# CANduino.net
KiCad netlist of a schematic drawn in Altium Designer
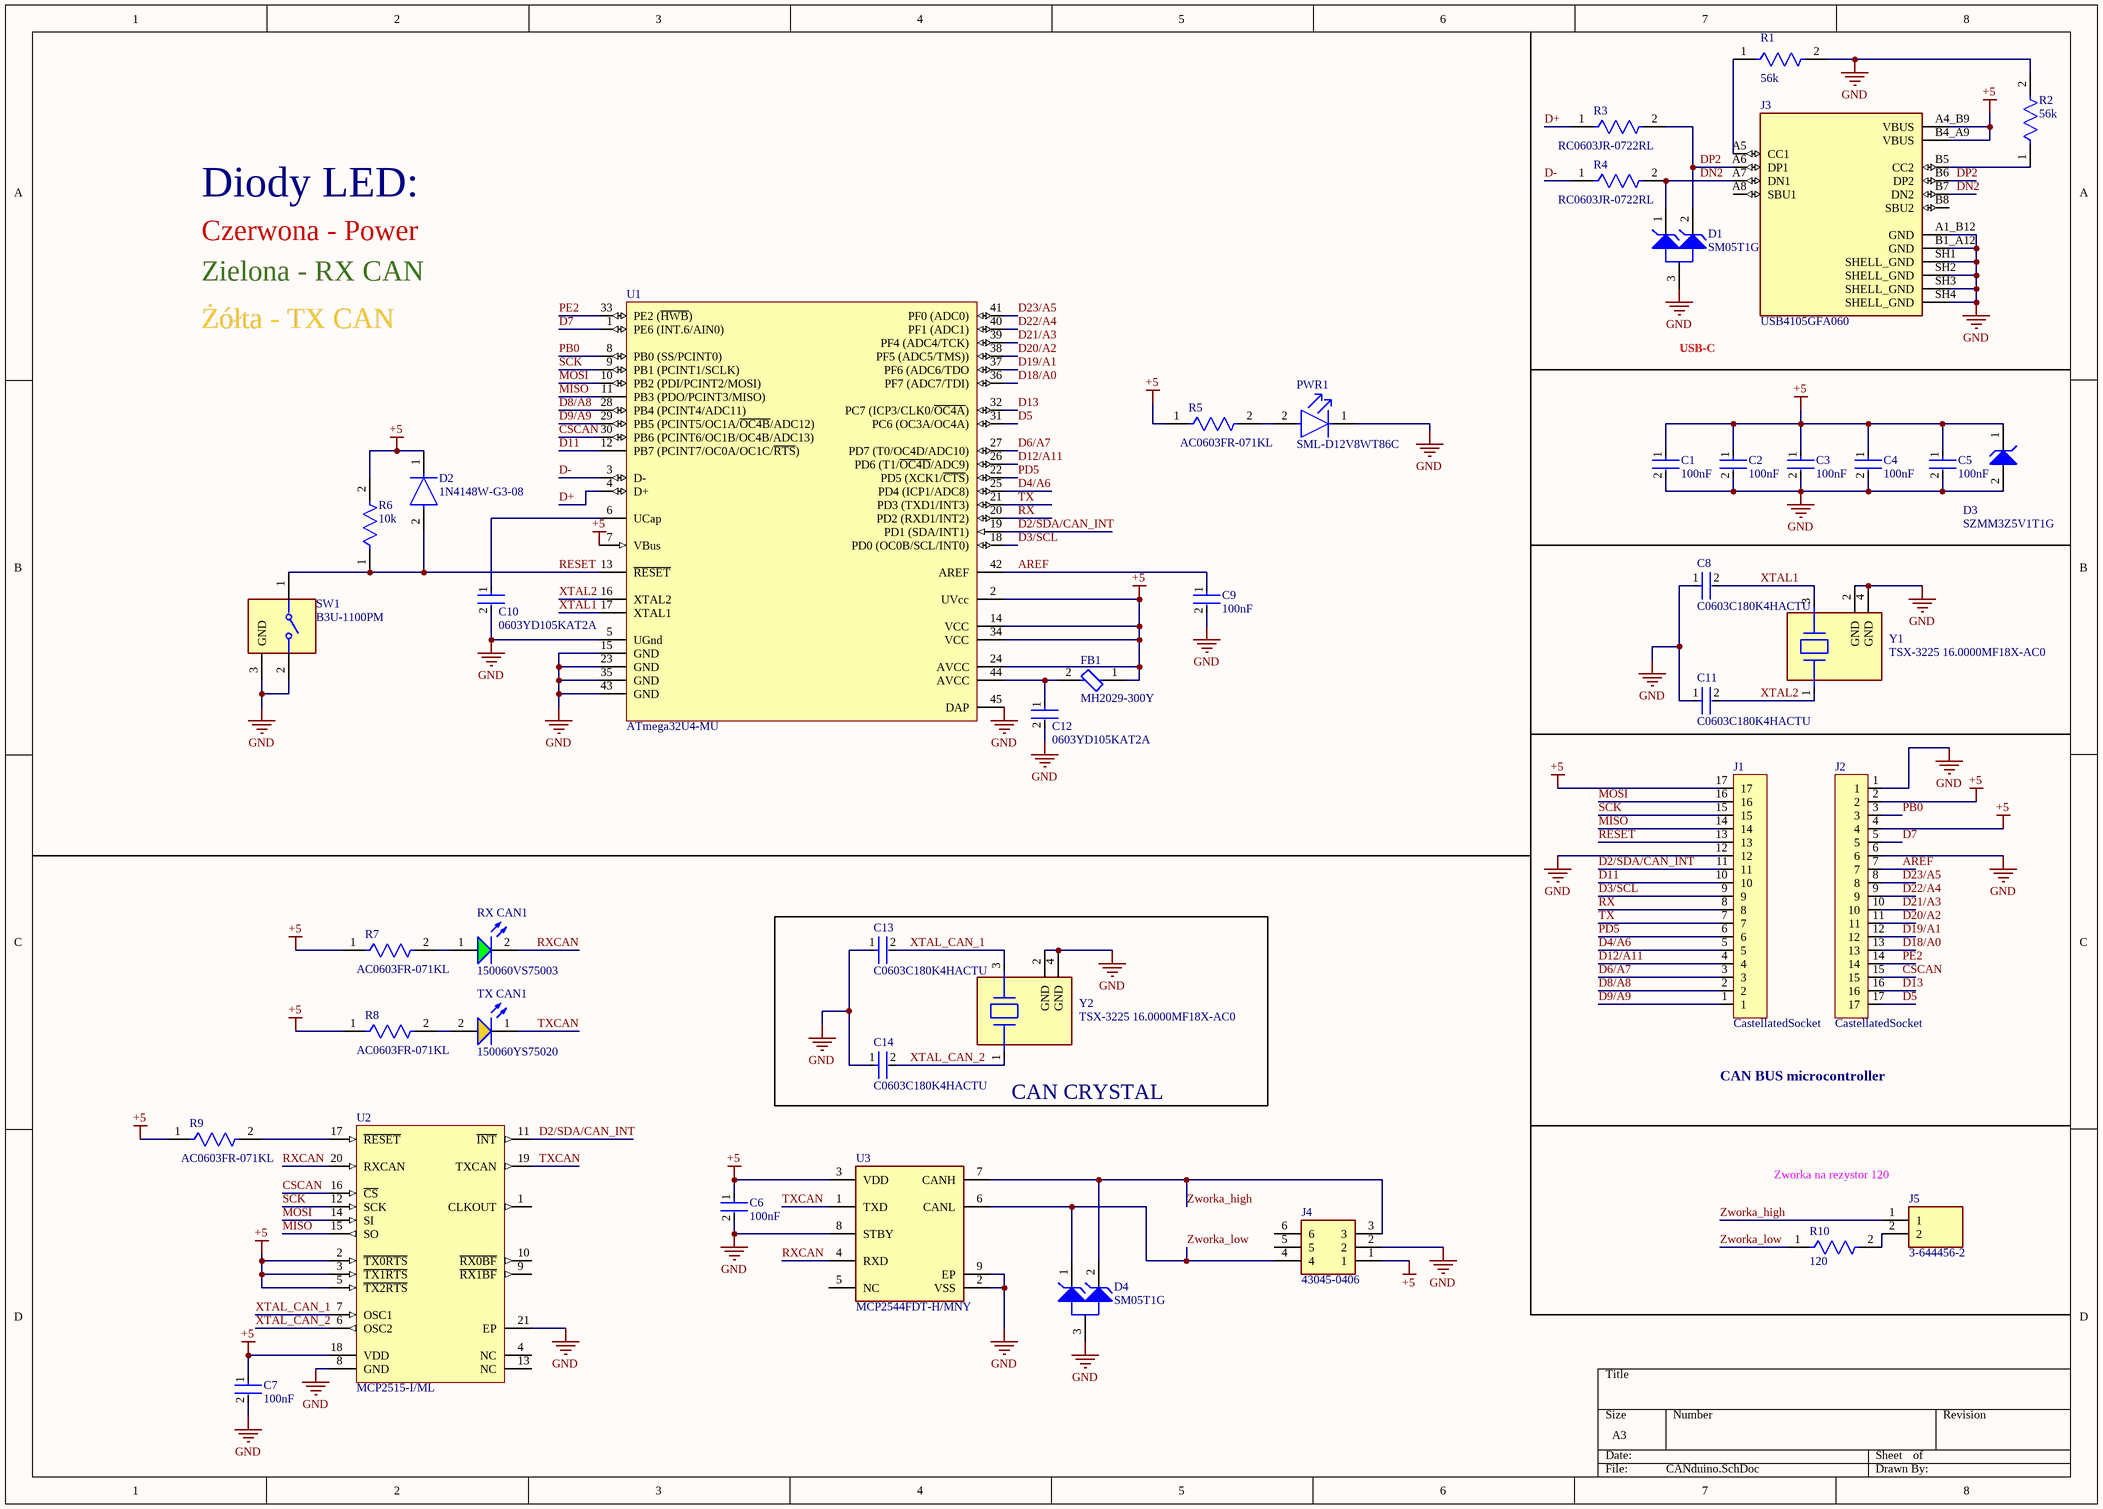
[diagram p0: CANduino.SchDoc]

(export (version "E")
  (design (tool "Eeschema 10.0.6"))
  (components
    (comp (ref "C1")
      (value "100nF")
      (footprint "FP-0603-L_1_6_0_1-W_0_8_0-IPC_C")
      (description "None")
      (fields (field (name "TOLERANCE") "10%"))
      (libsource (lib "Altium Content Vault") (part "02cd4be3c70576c341d710602a673aa"))
    )
    (comp (ref "C2")
      (value "100nF")
      (footprint "FP-0603-L_1_6_0_1-W_0_8_0-IPC_C")
      (description "None")
      (fields (field (name "TOLERANCE") "10%"))
      (libsource (lib "Altium Content Vault") (part "02cd4be3c70576c341d710602a673aa"))
    )
    (comp (ref "C3")
      (value "100nF")
      (footprint "FP-0603-L_1_6_0_1-W_0_8_0-IPC_C")
      (description "None")
      (fields (field (name "TOLERANCE") "10%"))
      (libsource (lib "Altium Content Vault") (part "02cd4be3c70576c341d710602a673aa"))
    )
    (comp (ref "C4")
      (value "100nF")
      (footprint "FP-0603-L_1_6_0_1-W_0_8_0-IPC_C")
      (description "None")
      (fields (field (name "TOLERANCE") "10%"))
      (libsource (lib "Altium Content Vault") (part "02cd4be3c70576c341d710602a673aa"))
    )
    (comp (ref "C5")
      (value "100nF")
      (footprint "FP-0603-L_1_6_0_1-W_0_8_0-IPC_C")
      (description "None")
      (fields (field (name "TOLERANCE") "10%"))
      (libsource (lib "Altium Content Vault") (part "02cd4be3c70576c341d710602a673aa"))
    )
    (comp (ref "C6")
      (value "100nF")
      (footprint "FP-0603-L_1_6_0_1-W_0_8_0-IPC_C")
      (description "None")
      (fields (field (name "TOLERANCE") "10%"))
      (libsource (lib "Altium Content Vault") (part "02cd4be3c70576c341d710602a673aa"))
    )
    (comp (ref "C7")
      (value "100nF")
      (footprint "FP-0603-L_1_6_0_1-W_0_8_0-IPC_C")
      (description "None")
      (fields (field (name "TOLERANCE") "10%"))
      (libsource (lib "Altium Content Vault") (part "02cd4be3c70576c341d710602a673aa"))
    )
    (comp (ref "C8")
      (value "C0603C180K4HACTU")
      (footprint "FP-C0603C-CF-MFG")
      (description "C0603 18 pF X8R 30ppm/°C 10.00% 16 V")
      (fields
        (field (name "TOLERANCE") "0.1")
        (field (name "OCTOPART") "https://octopart.com/c0603c180k4hactu-kemet-88725221")
      )
      (libsource (lib "Altium Content Vault") (part "b4654b650e69147ec39a6b967a45e02"))
    )
    (comp (ref "C9")
      (value "100nF")
      (footprint "FP-0603-L_1_6_0_1-W_0_8_0-IPC_C")
      (description "None")
      (fields (field (name "TOLERANCE") "10%"))
      (libsource (lib "Altium Content Vault") (part "02cd4be3c70576c341d710602a673aa"))
    )
    (comp (ref "C10")
      (value "0603YD105KAT2A")
      (footprint "FP-0603-L_1_6_0_15-W_0_81-IPC_B")
      (description "General Purpose Ceramic Capacitor, 0603, 1uF, 10%, X5R, 15%, 16V")
      (fields (field (name "VOLTAGE") "16V") (field (name "TOLERANCE") "10%"))
      (libsource (lib "Altium Content Vault") (part "02cd4be3c70576c341d710602a673aa"))
    )
    (comp (ref "C11")
      (value "C0603C180K4HACTU")
      (footprint "FP-C0603C-CF-MFG")
      (description "C0603 18 pF X8R 30ppm/°C 10.00% 16 V")
      (fields
        (field (name "TOLERANCE") "0.1")
        (field (name "OCTOPART") "https://octopart.com/c0603c180k4hactu-kemet-88725221")
      )
      (libsource (lib "Altium Content Vault") (part "b4654b650e69147ec39a6b967a45e02"))
    )
    (comp (ref "C12")
      (value "0603YD105KAT2A")
      (footprint "FP-0603-L_1_6_0_15-W_0_81-IPC_B")
      (description "General Purpose Ceramic Capacitor, 0603, 1uF, 10%, X5R, 15%, 16V")
      (fields (field (name "VOLTAGE") "16V") (field (name "TOLERANCE") "10%"))
      (libsource (lib "Altium Content Vault") (part "02cd4be3c70576c341d710602a673aa"))
    )
    (comp (ref "C13")
      (value "C0603C180K4HACTU")
      (footprint "FP-C0603C-CF-MFG")
      (description "C0603 18 pF X8R 30ppm/°C 10.00% 16 V")
      (fields
        (field (name "TOLERANCE") "0.1")
        (field (name "OCTOPART") "https://octopart.com/c0603c180k4hactu-kemet-88725221")
      )
      (libsource (lib "Altium Content Vault") (part "b4654b650e69147ec39a6b967a45e02"))
    )
    (comp (ref "C14")
      (value "C0603C180K4HACTU")
      (footprint "FP-C0603C-CF-MFG")
      (description "C0603 18 pF X8R 30ppm/°C 10.00% 16 V")
      (fields
        (field (name "TOLERANCE") "0.1")
        (field (name "OCTOPART") "https://octopart.com/c0603c180k4hactu-kemet-88725221")
      )
      (libsource (lib "Altium Content Vault") (part "b4654b650e69147ec39a6b967a45e02"))
    )
    (comp (ref "D1")
      (value "SM05T1G")
      (footprint "ONSC-SOT-23-3-318-08_V")
      (fields (field (name "MANUFACTURER") "On Semiconductor"))
      (libsource (lib "Altium Content Vault") (part "ONSC-K1K2A3-3"))
    )
    (comp (ref "D2")
      (value "1N4148W-G3-08")
      (footprint "FP-S8-V-3910_01-001-MFG")
      (description "1N4148W-G3-08 Rectifier Diode, 1 Phase, 1 Element, 0.15A, 100V V(RRM), Silicon")
      (libsource (lib "Altium Content Vault") (part "d7152d700b627762746794eb795d46e"))
    )
    (comp (ref "D3")
      (value "SZMM3Z5V1T1G")
      (footprint "ONSC-SOD-323-2-477-02_V")
      (description "Zener Voltage Regulator, 300 mW, 2-Pin SOD-323, Pb-Free, Tape and Reel")
      (fields (field (name "MANUFACTURER") "On Semiconductor"))
      (libsource (lib "Altium Content Vault") (part "ONSC-K1A2-2"))
    )
    (comp (ref "D4")
      (value "SM05T1G")
      (footprint "ONSC-SOT-23-3-318-08_V")
      (fields (field (name "MANUFACTURER") "On Semiconductor"))
      (libsource (lib "Altium Content Vault") (part "ONSC-K1K2A3-3"))
    )
    (comp (ref "FB1")
      (value "MH2029-300Y")
      (footprint "FP-MH2029-MFG")
      (description "FERRITE BEAD 30 OHM 0805 1LN")
      (fields
        (field (name "OCTOPART") "https://octopart.com/mh2029-300y-bourns-756929")
        (field (name "MANUFACTURER") "Bourns")
      )
      (libsource (lib "Altium Content Vault") (part "5f30dd21d616792df468990f7003faa"))
    )
    (comp (ref "J1")
      (value "CastellatedSocket")
      (footprint "Castellatedsocket")
      (libsource (lib "") (part "CastellatedSocket_1"))
    )
    (comp (ref "J2")
      (value "CastellatedSocket")
      (footprint "Castellatedsocket")
      (libsource (lib "Castellated") (part "CastellatedSocket"))
    )
    (comp (ref "J3")
      (value "USB4105GFA060")
      (footprint "GCT_USB4105GFA060")
      (fields (field (name "MF") "{'manufacturer': u'GCT'}"))
      (libsource (lib "rover_electronics") (part "USB4105GFA060"))
    )
    (comp (ref "J4")
      (value "43045-0406")
      (footprint "43045-04YY_060708_1")
      (description "Connector")
      (fields (field (name "MOUSER PART NUMBER") "538-43045-0406"))
      (libsource (lib "SamacSys") (part "43045-0406"))
    )
    (comp (ref "J5")
      (value "3-644456-2")
      (footprint "TE_3-644456-2")
      (description "Connector Unshrouded Header HDR 2 Position 2.54mm Solder Straight Thru-Hole")
      (fields (field (name "MF") "TE Connectivity") (field (name "DIGI-KEY_PART_NUMBER") "A31112-ND"))
      (libsource (lib "rover_electronics") (part "3-644456-2"))
    )
    (comp (ref "PWR1")
      (value "SML-D12V8WT86C")
      (footprint "FP-SML-D12-MFG")
      (description "LED RED 1608 SMD")
      (libsource (lib "Altium Content Vault") (part "8706943c75ba83719d021d2fdc84c58"))
    )
    (comp (ref "R1")
      (value "56k")
      (footprint "FP-RR0816-IPC_C")
      (description "56kΩ ±0.5% 0.0625W 1/16W Chip Resistor 0603 (1608 Metric) Thin Film")
      (fields (field (name "TOLERANCE") "0.5%"))
      (libsource (lib "Altium Content Vault") (part "1029c3af85768c4190bb7ad29bc67b5"))
    )
    (comp (ref "R2")
      (value "56k")
      (footprint "FP-RR0816-IPC_C")
      (description "56kΩ ±0.5% 0.0625W 1/16W Chip Resistor 0603 (1608 Metric) Thin Film")
      (fields (field (name "TOLERANCE") "0.5%"))
      (libsource (lib "Altium Content Vault") (part "1029c3af85768c4190bb7ad29bc67b5"))
    )
    (comp (ref "R3")
      (value "RC0603JR-0722RL")
      (footprint "FP-RC0603-0_55-IPC_C")
      (description "RES SMD 22 OHM 5% 1/10W 0603")
      (fields (field (name "TOLERANCE") "5%"))
      (libsource (lib "Altium Content Vault") (part "1029c3af85768c4190bb7ad29bc67b5"))
    )
    (comp (ref "R4")
      (value "RC0603JR-0722RL")
      (footprint "FP-RC0603-0_55-IPC_C")
      (description "RES SMD 22 OHM 5% 1/10W 0603")
      (fields (field (name "TOLERANCE") "5%"))
      (libsource (lib "Altium Content Vault") (part "1029c3af85768c4190bb7ad29bc67b5"))
    )
    (comp (ref "R5")
      (value "AC0603FR-071KL")
      (footprint "FP-AC0603-IPC_B")
      (description "RES 1kΩ 1.00% 0.1W 0603")
      (fields (field (name "TOLERANCE") "1%"))
      (libsource (lib "Altium Content Vault") (part "1029c3af85768c4190bb7ad29bc67b5"))
    )
    (comp (ref "R6")
      (value "10k")
      (footprint "FP-MCT0603-IPC_C")
      (description "RES SMD 100 OHM 1% 1/8W 0603")
      (fields (field (name "TOLERANCE") "1%"))
      (libsource (lib "Altium Content Vault") (part "1029c3af85768c4190bb7ad29bc67b5"))
    )
    (comp (ref "R7")
      (value "AC0603FR-071KL")
      (footprint "FP-AC0603-IPC_B")
      (description "RES 1kΩ 1.00% 0.1W 0603")
      (fields (field (name "TOLERANCE") "1%"))
      (libsource (lib "Altium Content Vault") (part "1029c3af85768c4190bb7ad29bc67b5"))
    )
    (comp (ref "R8")
      (value "AC0603FR-071KL")
      (footprint "FP-AC0603-IPC_B")
      (description "RES 1kΩ 1.00% 0.1W 0603")
      (fields (field (name "TOLERANCE") "1%"))
      (libsource (lib "Altium Content Vault") (part "1029c3af85768c4190bb7ad29bc67b5"))
    )
    (comp (ref "R9")
      (value "AC0603FR-071KL")
      (footprint "FP-AC0603-IPC_B")
      (description "RES 1kΩ 1.00% 0.1W 0603")
      (fields (field (name "TOLERANCE") "1%"))
      (libsource (lib "Altium Content Vault") (part "1029c3af85768c4190bb7ad29bc67b5"))
    )
    (comp (ref "R10")
      (value "120")
      (footprint "FP-CRCW0603-e3-MFG")
      (description "RES Thick Film, 120Ω, 1%, 0.1W, 100ppm/°C, 0603")
      (fields (field (name "TOLERANCE") "1%"))
      (libsource (lib "Altium Content Vault") (part "1029c3af85768c4190bb7ad29bc67b5"))
    )
    (comp (ref "RX CAN1")
      (value "150060VS75003")
      (footprint "WL-SMCW_0603_150060xx75003")
      (description "Led, Bright Green, 100Mcd, 572Nm Rohs Compliant: Yes")
      (libsource (lib "Altium Content Vault") (part "LED_Green_1A-2K"))
    )
    (comp (ref "SW1")
      (value "B3U-1100PM")
      (footprint "FP-B3U-1100PM-MFG")
      (description "SWITCH TACTILE SPST-NO 0.05A 12V")
      (libsource (lib "Altium Content Vault") (part "6d7322ea62e06c21cb959ab9578dfa0"))
    )
    (comp (ref "TX CAN1")
      (value "150060YS75020")
      (footprint "WL-SMCW_0603_150060xx75020")
      (description "WL-SMCW SMT Mono-Color Chip LED Waterclear super f")
      (libsource (lib "Altium Content Vault") (part "LED_Yellow_2A-1K"))
    )
    (comp (ref "U1")
      (value "ATmega32U4-MU")
      (footprint "44PW_M")
      (libsource (lib "Altium Content Vault") (part "MC-8B-ATM16U4-SQ45"))
    )
    (comp (ref "U2")
      (value "MCP2515-I/ML")
      (footprint "QFN-ML20_L")
      (description "Stand-Alone CAN Controller With SPI Interface, 20-Pin QFN, Industrial Temperature")
      (libsource (lib "Altium Content Vault") (part "COM-CAN-MCP2515-21"))
    )
    (comp (ref "U3")
      (value "MCP2544FDT-H/MNY")
      (footprint "FP-C04-129-MNY-MFG")
      (description "IC TRANSCEIVER 1/1 8TDFN")
      (libsource (lib "Altium Content Vault") (part "4800a2c73585bbd998bf1dde7dcf233"))
    )
    (comp (ref "Y1")
      (value "TSX-3225 16.0000MF18X-AC0")
      (footprint "FP-TSX-3225-MFG")
      (description "CRYSTAL 16.00 MHZ 9PF SMD")
      (fields
        (field (name "OCTOPART") "https://octopart.com/tsx-3225+16.0000mf18x-ac0-epson-58756552")
        (field (name "MANUFACTURER") "EPSON")
      )
      (libsource (lib "Altium Content Vault") (part "a9e65936d6f6a8cd8abf4b50f2664b9"))
    )
    (comp (ref "Y2")
      (value "TSX-3225 16.0000MF18X-AC0")
      (footprint "FP-TSX-3225-MFG")
      (description "CRYSTAL 16.00 MHZ 9PF SMD")
      (fields
        (field (name "OCTOPART") "https://octopart.com/tsx-3225+16.0000mf18x-ac0-epson-58756552")
        (field (name "MANUFACTURER") "EPSON")
      )
      (libsource (lib "Altium Content Vault") (part "a9e65936d6f6a8cd8abf4b50f2664b9"))
    )
  )
  (nets
    (net (code "1") (name "+5") (class "Default")
      (node (ref "C1") (pin "1") (pinfunction "1_1") (pintype "passive"))
      (node (ref "C2") (pin "1") (pinfunction "1_1") (pintype "passive"))
      (node (ref "C3") (pin "1") (pinfunction "1_1") (pintype "passive"))
      (node (ref "C4") (pin "1") (pinfunction "1_1") (pintype "passive"))
      (node (ref "C5") (pin "1") (pinfunction "1_1") (pintype "passive"))
      (node (ref "C6") (pin "1") (pinfunction "1_1") (pintype "passive"))
      (node (ref "C7") (pin "1") (pinfunction "1_1") (pintype "passive"))
      (node (ref "D2") (pin "1") (pinfunction "C_1") (pintype "passive"))
      (node (ref "D3") (pin "1") (pinfunction "K_1") (pintype "passive"))
      (node (ref "FB1") (pin "1") (pinfunction "1_1") (pintype "passive"))
      (node (ref "J1") (pin "17") (pinfunction "17_17") (pintype "passive"))
      (node (ref "J2") (pin "2") (pinfunction "2_2") (pintype "passive"))
      (node (ref "J2") (pin "4") (pinfunction "4_4") (pintype "passive"))
      (node (ref "J3") (pin "A4_B9") (pinfunction "VBUS_A4_B9") (pintype "power_in"))
      (node (ref "J3") (pin "B4_A9") (pinfunction "VBUS_B4_A9") (pintype "power_in"))
      (node (ref "J4") (pin "1") (pinfunction "1_1") (pintype "passive"))
      (node (ref "R5") (pin "1") (pinfunction "1_1") (pintype "passive"))
      (node (ref "R6") (pin "2") (pinfunction "2_2") (pintype "passive"))
      (node (ref "R7") (pin "1") (pinfunction "1_1") (pintype "passive"))
      (node (ref "R8") (pin "1") (pinfunction "1_1") (pintype "passive"))
      (node (ref "R9") (pin "1") (pinfunction "1_1") (pintype "passive"))
      (node (ref "U1") (pin "14") (pinfunction "VCC_14") (pintype "power_in"))
      (node (ref "U1") (pin "2") (pinfunction "UVcc_2") (pintype "power_in"))
      (node (ref "U1") (pin "24") (pinfunction "AVCC_24") (pintype "power_in"))
      (node (ref "U1") (pin "34") (pinfunction "VCC_34") (pintype "power_in"))
      (node (ref "U1") (pin "7") (pinfunction "VBus_7") (pintype "input"))
      (node (ref "U2") (pin "18") (pinfunction "VDD_18") (pintype "power_in"))
      (node (ref "U2") (pin "2") (pinfunction "~{TX0RTS}_2") (pintype "input"))
      (node (ref "U2") (pin "3") (pinfunction "~{TX1RTS}_3") (pintype "input"))
      (node (ref "U2") (pin "5") (pinfunction "~{TX2RTS}_5") (pintype "input"))
      (node (ref "U3") (pin "3") (pinfunction "VDD_3") (pintype "power_in"))
    )
    (net (code "3") (name "/AREF") (class "Default")
      (node (ref "C9") (pin "1") (pinfunction "1_1") (pintype "passive"))
      (node (ref "J2") (pin "7") (pinfunction "7_7") (pintype "passive"))
      (node (ref "U1") (pin "42") (pinfunction "AREF_42") (pintype "passive"))
    )
    (net (code "4") (name "/CSCAN") (class "Default")
      (node (ref "J2") (pin "15") (pinfunction "15_15") (pintype "passive"))
      (node (ref "U1") (pin "30") (pinfunction "PB6_(PCINT6/OC1B/OC4B/ADC13)_30") (pintype "bidirectional"))
      (node (ref "U2") (pin "16") (pinfunction "~{CS}_16") (pintype "input"))
    )
    (net (code "5") (name "/D+") (class "Default")
      (node (ref "R3") (pin "1") (pinfunction "1_1") (pintype "passive"))
      (node (ref "U1") (pin "4") (pinfunction "D+_4") (pintype "bidirectional"))
    )
    (net (code "6") (name "/D-") (class "Default")
      (node (ref "R4") (pin "1") (pinfunction "1_1") (pintype "passive"))
      (node (ref "U1") (pin "3") (pinfunction "D-_3") (pintype "bidirectional"))
    )
    (net (code "7") (name "/D2{slash}SDA{slash}CAN_INT") (class "Default")
      (node (ref "J1") (pin "11") (pinfunction "11_11") (pintype "passive"))
      (node (ref "U1") (pin "19") (pinfunction "PD1_(SDA/INT1)_19") (pintype "input"))
      (node (ref "U2") (pin "11") (pinfunction "~{INT}_11") (pintype "output"))
    )
    (net (code "8") (name "/D3{slash}SCL") (class "Default")
      (node (ref "J1") (pin "9") (pinfunction "9_9") (pintype "passive"))
      (node (ref "U1") (pin "18") (pinfunction "PD0_(OC0B/SCL/INT0)_18") (pintype "bidirectional"))
    )
    (net (code "9") (name "/D4{slash}A6") (class "Default")
      (node (ref "J1") (pin "5") (pinfunction "5_5") (pintype "passive"))
      (node (ref "U1") (pin "25") (pinfunction "PD4_(ICP1/ADC8)_25") (pintype "bidirectional"))
    )
    (net (code "10") (name "/D5") (class "Default")
      (node (ref "J2") (pin "17") (pinfunction "17_17") (pintype "passive"))
      (node (ref "U1") (pin "31") (pinfunction "PC6_(OC3A/OC4A)_31") (pintype "bidirectional"))
    )
    (net (code "11") (name "/D6{slash}A7") (class "Default")
      (node (ref "J1") (pin "3") (pinfunction "3_3") (pintype "passive"))
      (node (ref "U1") (pin "27") (pinfunction "PD7_(T0/OC4D/ADC10)_27") (pintype "bidirectional"))
    )
    (net (code "12") (name "/D7") (class "Default")
      (node (ref "J2") (pin "5") (pinfunction "5_5") (pintype "passive"))
      (node (ref "U1") (pin "1") (pinfunction "PE6_(INT.6/AIN0)_1") (pintype "bidirectional"))
    )
    (net (code "13") (name "/D8{slash}A8") (class "Default")
      (node (ref "J1") (pin "2") (pinfunction "2_2") (pintype "passive"))
      (node (ref "U1") (pin "28") (pinfunction "PB4_(PCINT4/ADC11)_28") (pintype "bidirectional"))
    )
    (net (code "14") (name "/D9{slash}A9") (class "Default")
      (node (ref "J1") (pin "1") (pinfunction "1_1") (pintype "passive"))
      (node (ref "U1") (pin "29") (pinfunction "PB5_(PCINT5/OC1A/~{OC4B}/ADC12)_29") (pintype "bidirectional"))
    )
    (net (code "15") (name "/D11") (class "Default")
      (node (ref "J1") (pin "10") (pinfunction "10_10") (pintype "passive"))
      (node (ref "U1") (pin "12") (pinfunction "PB7_(PCINT7/OC0A/OC1C/~{RTS})_12") (pintype "passive"))
    )
    (net (code "16") (name "/D12{slash}A11") (class "Default")
      (node (ref "J1") (pin "4") (pinfunction "4_4") (pintype "passive"))
      (node (ref "U1") (pin "26") (pinfunction "PD6_(T1/~{OC4D}/ADC9)_26") (pintype "bidirectional"))
    )
    (net (code "17") (name "/D13") (class "Default")
      (node (ref "J2") (pin "16") (pinfunction "16_16") (pintype "passive"))
      (node (ref "U1") (pin "32") (pinfunction "PC7_(ICP3/CLK0/~{OC4A})_32") (pintype "bidirectional"))
    )
    (net (code "18") (name "/D18{slash}A0") (class "Default")
      (node (ref "J2") (pin "13") (pinfunction "13_13") (pintype "passive"))
      (node (ref "U1") (pin "36") (pinfunction "PF7_(ADC7/TDI)_36") (pintype "bidirectional"))
    )
    (net (code "19") (name "/D19{slash}A1") (class "Default")
      (node (ref "J2") (pin "12") (pinfunction "12_12") (pintype "passive"))
      (node (ref "U1") (pin "37") (pinfunction "PF6_(ADC6/TDO_37") (pintype "bidirectional"))
    )
    (net (code "20") (name "/D20{slash}A2") (class "Default")
      (node (ref "J2") (pin "11") (pinfunction "11_11") (pintype "passive"))
      (node (ref "U1") (pin "38") (pinfunction "PF5_(ADC5/TMS))_38") (pintype "bidirectional"))
    )
    (net (code "21") (name "/D21{slash}A3") (class "Default")
      (node (ref "J2") (pin "10") (pinfunction "10_10") (pintype "passive"))
      (node (ref "U1") (pin "39") (pinfunction "PF4_(ADC4/TCK)_39") (pintype "bidirectional"))
    )
    (net (code "22") (name "/D22{slash}A4") (class "Default")
      (node (ref "J2") (pin "9") (pinfunction "9_9") (pintype "passive"))
      (node (ref "U1") (pin "40") (pinfunction "PF1_(ADC1)_40") (pintype "bidirectional"))
    )
    (net (code "23") (name "/D23{slash}A5") (class "Default")
      (node (ref "J2") (pin "8") (pinfunction "8_8") (pintype "passive"))
      (node (ref "U1") (pin "41") (pinfunction "PF0_(ADC0)_41") (pintype "bidirectional"))
    )
    (net (code "24") (name "/DN2") (class "Default")
      (node (ref "D1") (pin "1") (pinfunction "K1_1") (pintype "passive"))
      (node (ref "J3") (pin "A7") (pinfunction "DN1_A7") (pintype "bidirectional"))
      (node (ref "J3") (pin "B7") (pinfunction "DN2_B7") (pintype "bidirectional"))
      (node (ref "R4") (pin "2") (pinfunction "2_2") (pintype "passive"))
    )
    (net (code "25") (name "/DP2") (class "Default")
      (node (ref "D1") (pin "2") (pinfunction "K2_2") (pintype "passive"))
      (node (ref "J3") (pin "A6") (pinfunction "DP1_A6") (pintype "bidirectional"))
      (node (ref "J3") (pin "B6") (pinfunction "DP2_B6") (pintype "bidirectional"))
      (node (ref "R3") (pin "2") (pinfunction "2_2") (pintype "passive"))
    )
    (net (code "26") (name "/MISO") (class "Default")
      (node (ref "J1") (pin "14") (pinfunction "14_14") (pintype "passive"))
      (node (ref "U1") (pin "11") (pinfunction "PB3_(PDO/PCINT3/MISO)_11") (pintype "passive"))
      (node (ref "U2") (pin "15") (pinfunction "SO_15") (pintype "output"))
    )
    (net (code "27") (name "/MOSI") (class "Default")
      (node (ref "J1") (pin "16") (pinfunction "16_16") (pintype "passive"))
      (node (ref "U1") (pin "10") (pinfunction "PB2_(PDI/PCINT2/MOSI)_10") (pintype "bidirectional"))
      (node (ref "U2") (pin "14") (pinfunction "SI_14") (pintype "input"))
    )
    (net (code "28") (name "/PB0") (class "Default")
      (node (ref "J2") (pin "3") (pinfunction "3_3") (pintype "passive"))
      (node (ref "U1") (pin "8") (pinfunction "PB0_(SS/PCINT0)_8") (pintype "bidirectional"))
    )
    (net (code "29") (name "/PD5") (class "Default")
      (node (ref "J1") (pin "6") (pinfunction "6_6") (pintype "passive"))
      (node (ref "U1") (pin "22") (pinfunction "PD5_(XCK1/~{CTS})_22") (pintype "bidirectional"))
    )
    (net (code "30") (name "/PE2") (class "Default")
      (node (ref "J2") (pin "14") (pinfunction "14_14") (pintype "passive"))
      (node (ref "U1") (pin "33") (pinfunction "PE2_(~{HWB})_33") (pintype "bidirectional"))
    )
    (net (code "31") (name "/RESET") (class "Default")
      (node (ref "D2") (pin "2") (pinfunction "A_2") (pintype "passive"))
      (node (ref "J1") (pin "13") (pinfunction "13_13") (pintype "passive"))
      (node (ref "R6") (pin "1") (pinfunction "1_1") (pintype "passive"))
      (node (ref "SW1") (pin "1") (pinfunction "1_1") (pintype "passive"))
      (node (ref "U1") (pin "13") (pinfunction "~{RESET}_13") (pintype "passive"))
    )
    (net (code "32") (name "/RX") (class "Default")
      (node (ref "J1") (pin "8") (pinfunction "8_8") (pintype "passive"))
      (node (ref "U1") (pin "20") (pinfunction "PD2_(RXD1/INT2)_20") (pintype "bidirectional"))
    )
    (net (code "33") (name "/RXCAN") (class "Default")
      (node (ref "RX CAN1") (pin "2") (pinfunction "K_2") (pintype "passive"))
      (node (ref "U2") (pin "20") (pinfunction "RXCAN_20") (pintype "input"))
      (node (ref "U3") (pin "4") (pinfunction "RXD_4") (pintype "passive"))
    )
    (net (code "34") (name "/SCK") (class "Default")
      (node (ref "J1") (pin "15") (pinfunction "15_15") (pintype "passive"))
      (node (ref "U1") (pin "9") (pinfunction "PB1_(PCINT1/SCLK)_9") (pintype "bidirectional"))
      (node (ref "U2") (pin "12") (pinfunction "SCK_12") (pintype "input"))
    )
    (net (code "35") (name "/TX") (class "Default")
      (node (ref "J1") (pin "7") (pinfunction "7_7") (pintype "passive"))
      (node (ref "U1") (pin "21") (pinfunction "PD3_(TXD1/INT3)_21") (pintype "bidirectional"))
    )
    (net (code "36") (name "/TXCAN") (class "Default")
      (node (ref "TX CAN1") (pin "1") (pinfunction "K_1") (pintype "passive"))
      (node (ref "U2") (pin "19") (pinfunction "TXCAN_19") (pintype "output"))
      (node (ref "U3") (pin "1") (pinfunction "TXD_1") (pintype "passive"))
    )
    (net (code "37") (name "/XTAL1") (class "Default")
      (node (ref "C8") (pin "2") (pinfunction "2_2") (pintype "passive"))
      (node (ref "U1") (pin "17") (pinfunction "XTAL1_17") (pintype "passive"))
      (node (ref "Y1") (pin "3") (pinfunction "3_3") (pintype "passive"))
    )
    (net (code "38") (name "/XTAL2") (class "Default")
      (node (ref "C11") (pin "2") (pinfunction "2_2") (pintype "passive"))
      (node (ref "U1") (pin "16") (pinfunction "XTAL2_16") (pintype "passive"))
      (node (ref "Y1") (pin "1") (pinfunction "1_1") (pintype "passive"))
    )
    (net (code "39") (name "/XTAL_CAN_1") (class "Default")
      (node (ref "C13") (pin "2") (pinfunction "2_2") (pintype "passive"))
      (node (ref "U2") (pin "7") (pinfunction "OSC1_7") (pintype "input"))
      (node (ref "Y2") (pin "3") (pinfunction "3_3") (pintype "passive"))
    )
    (net (code "40") (name "/XTAL_CAN_2") (class "Default")
      (node (ref "C14") (pin "2") (pinfunction "2_2") (pintype "passive"))
      (node (ref "U2") (pin "6") (pinfunction "OSC2_6") (pintype "output"))
      (node (ref "Y2") (pin "1") (pinfunction "1_1") (pintype "passive"))
    )
    (net (code "41") (name "/Zworka_high") (class "Default")
      (node (ref "D4") (pin "2") (pinfunction "K2_2") (pintype "passive"))
      (node (ref "J4") (pin "3") (pinfunction "3_3") (pintype "passive"))
      (node (ref "J5") (pin "1") (pinfunction "1_1") (pintype "passive"))
      (node (ref "U3") (pin "7") (pinfunction "CANH_7") (pintype "passive"))
    )
    (net (code "42") (name "/Zworka_low") (class "Default")
      (node (ref "D4") (pin "1") (pinfunction "K1_1") (pintype "passive"))
      (node (ref "J4") (pin "4") (pinfunction "4_4") (pintype "passive"))
      (node (ref "R10") (pin "1") (pinfunction "1_1") (pintype "passive"))
      (node (ref "U3") (pin "6") (pinfunction "CANL_6") (pintype "passive"))
    )
    (net (code "43") (name "GND") (class "Default")
      (node (ref "C1") (pin "2") (pinfunction "2_2") (pintype "passive"))
      (node (ref "C10") (pin "2") (pinfunction "2_2") (pintype "passive"))
      (node (ref "C11") (pin "1") (pinfunction "1_1") (pintype "passive"))
      (node (ref "C12") (pin "2") (pinfunction "2_2") (pintype "passive"))
      (node (ref "C13") (pin "1") (pinfunction "1_1") (pintype "passive"))
      (node (ref "C14") (pin "1") (pinfunction "1_1") (pintype "passive"))
      (node (ref "C2") (pin "2") (pinfunction "2_2") (pintype "passive"))
      (node (ref "C3") (pin "2") (pinfunction "2_2") (pintype "passive"))
      (node (ref "C4") (pin "2") (pinfunction "2_2") (pintype "passive"))
      (node (ref "C5") (pin "2") (pinfunction "2_2") (pintype "passive"))
      (node (ref "C6") (pin "2") (pinfunction "2_2") (pintype "passive"))
      (node (ref "C7") (pin "2") (pinfunction "2_2") (pintype "passive"))
      (node (ref "C8") (pin "1") (pinfunction "1_1") (pintype "passive"))
      (node (ref "C9") (pin "2") (pinfunction "2_2") (pintype "passive"))
      (node (ref "D1") (pin "3") (pinfunction "A_3") (pintype "passive"))
      (node (ref "D3") (pin "2") (pinfunction "A_2") (pintype "passive"))
      (node (ref "D4") (pin "3") (pinfunction "A_3") (pintype "passive"))
      (node (ref "J1") (pin "12") (pinfunction "12_12") (pintype "passive"))
      (node (ref "J2") (pin "1") (pinfunction "1_1") (pintype "passive"))
      (node (ref "J2") (pin "6") (pinfunction "6_6") (pintype "passive"))
      (node (ref "J3") (pin "A1_B12") (pinfunction "GND_A1_B12") (pintype "power_in"))
      (node (ref "J3") (pin "B1_A12") (pinfunction "GND_B1_A12") (pintype "power_in"))
      (node (ref "J3") (pin "SH1") (pinfunction "SHELL_GND_SH1") (pintype "power_in"))
      (node (ref "J3") (pin "SH2") (pinfunction "SHELL_GND_SH2") (pintype "power_in"))
      (node (ref "J3") (pin "SH3") (pinfunction "SHELL_GND_SH3") (pintype "power_in"))
      (node (ref "J3") (pin "SH4") (pinfunction "SHELL_GND_SH4") (pintype "power_in"))
      (node (ref "J4") (pin "2") (pinfunction "2_2") (pintype "passive"))
      (node (ref "PWR1") (pin "1") (pinfunction "C_1") (pintype "passive"))
      (node (ref "R1") (pin "2") (pinfunction "2_2") (pintype "passive"))
      (node (ref "R2") (pin "2") (pinfunction "2_2") (pintype "passive"))
      (node (ref "SW1") (pin "2") (pinfunction "2_2") (pintype "passive"))
      (node (ref "SW1") (pin "3") (pinfunction "GND_3") (pintype "power_in"))
      (node (ref "U1") (pin "15") (pinfunction "GND_15") (pintype "power_in"))
      (node (ref "U1") (pin "23") (pinfunction "GND_23") (pintype "power_in"))
      (node (ref "U1") (pin "35") (pinfunction "GND_35") (pintype "power_in"))
      (node (ref "U1") (pin "43") (pinfunction "GND_43") (pintype "power_in"))
      (node (ref "U1") (pin "45") (pinfunction "DAP_45") (pintype "power_in"))
      (node (ref "U1") (pin "5") (pinfunction "UGnd_5") (pintype "power_in"))
      (node (ref "U2") (pin "21") (pinfunction "EP_21") (pintype "passive"))
      (node (ref "U2") (pin "8") (pinfunction "GND_8") (pintype "power_in"))
      (node (ref "U3") (pin "2") (pinfunction "VSS_2") (pintype "power_in"))
      (node (ref "U3") (pin "8") (pinfunction "STBY_8") (pintype "passive"))
      (node (ref "U3") (pin "9") (pinfunction "EP_9") (pintype "passive"))
      (node (ref "Y1") (pin "2") (pinfunction "GND_2") (pintype "power_in"))
      (node (ref "Y1") (pin "4") (pinfunction "GND_4") (pintype "power_in"))
      (node (ref "Y2") (pin "2") (pinfunction "GND_2") (pintype "power_in"))
      (node (ref "Y2") (pin "4") (pinfunction "GND_4") (pintype "power_in"))
    )
    (net (code "44") (name "Net-(C12-Pad1)") (class "Default")
      (node (ref "C12") (pin "1") (pinfunction "1_1") (pintype "passive"))
      (node (ref "FB1") (pin "2") (pinfunction "2_2") (pintype "passive"))
      (node (ref "U1") (pin "44") (pinfunction "AVCC_44") (pintype "power_in"))
    )
    (net (code "45") (name "Net-(J3-CC1)") (class "Default")
      (node (ref "J3") (pin "A5") (pinfunction "CC1_A5") (pintype "bidirectional"))
      (node (ref "R1") (pin "1") (pinfunction "1_1") (pintype "passive"))
    )
    (net (code "46") (name "Net-(J3-CC2)") (class "Default")
      (node (ref "J3") (pin "B5") (pinfunction "CC2_B5") (pintype "bidirectional"))
      (node (ref "R2") (pin "1") (pinfunction "1_1") (pintype "passive"))
    )
    (net (code "47") (name "Net-(J5-Pad2)") (class "Default")
      (node (ref "J5") (pin "2") (pinfunction "2_2") (pintype "passive"))
      (node (ref "R10") (pin "2") (pinfunction "2_2") (pintype "passive"))
    )
    (net (code "48") (name "Net-(PWR1-A)") (class "Default")
      (node (ref "PWR1") (pin "2") (pinfunction "A_2") (pintype "passive"))
      (node (ref "R5") (pin "2") (pinfunction "2_2") (pintype "passive"))
    )
    (net (code "49") (name "Net-(RX CAN1-A)") (class "Default")
      (node (ref "R7") (pin "2") (pinfunction "2_2") (pintype "passive"))
      (node (ref "RX CAN1") (pin "1") (pinfunction "A_1") (pintype "passive"))
    )
    (net (code "50") (name "Net-(TX CAN1-A)") (class "Default")
      (node (ref "R8") (pin "2") (pinfunction "2_2") (pintype "passive"))
      (node (ref "TX CAN1") (pin "2") (pinfunction "A_2") (pintype "passive"))
    )
    (net (code "51") (name "Net-(U1-UCap)") (class "Default")
      (node (ref "C10") (pin "1") (pinfunction "1_1") (pintype "passive"))
      (node (ref "U1") (pin "6") (pinfunction "UCap_6") (pintype "passive"))
    )
    (net (code "52") (name "Net-(U2-~{RESET})") (class "Default")
      (node (ref "R9") (pin "2") (pinfunction "2_2") (pintype "passive"))
      (node (ref "U2") (pin "17") (pinfunction "~{RESET}_17") (pintype "input"))
    )
    (net (code "53") (name "unconnected-(J3-SBU1-PadA8)") (class "Default")
      (node (ref "J3") (pin "A8") (pinfunction "SBU1_A8") (pintype "bidirectional"))
    )
    (net (code "54") (name "unconnected-(J3-SBU2-PadB8)") (class "Default")
      (node (ref "J3") (pin "B8") (pinfunction "SBU2_B8") (pintype "bidirectional"))
    )
    (net (code "55") (name "unconnected-(J4-Pad5)") (class "Default")
      (node (ref "J4") (pin "5") (pinfunction "5_5") (pintype "passive"))
    )
    (net (code "56") (name "unconnected-(J4-Pad6)") (class "Default")
      (node (ref "J4") (pin "6") (pinfunction "6_6") (pintype "passive"))
    )
    (net (code "57") (name "unconnected-(U2-CLKOUT-Pad1)") (class "Default")
      (node (ref "U2") (pin "1") (pinfunction "CLKOUT_1") (pintype "output"))
    )
    (net (code "58") (name "unconnected-(U2-NC-Pad4)") (class "Default")
      (node (ref "U2") (pin "4") (pinfunction "NC_4") (pintype "passive"))
    )
    (net (code "59") (name "unconnected-(U2-NC-Pad13)") (class "Default")
      (node (ref "U2") (pin "13") (pinfunction "NC_13") (pintype "passive"))
    )
    (net (code "60") (name "unconnected-(U2-~{RX0BF}-Pad10)") (class "Default")
      (node (ref "U2") (pin "10") (pinfunction "~{RX0BF}_10") (pintype "output"))
    )
    (net (code "61") (name "unconnected-(U2-~{RX1BF}-Pad9)") (class "Default")
      (node (ref "U2") (pin "9") (pinfunction "~{RX1BF}_9") (pintype "output"))
    )
    (net (code "62") (name "unconnected-(U3-NC-Pad5)") (class "Default")
      (node (ref "U3") (pin "5") (pinfunction "NC_5") (pintype "passive"))
    )
  )
)
